# 6-PadsControl_CodSwitch.net
KiCad netlist of a schematic drawn in Altium Designer
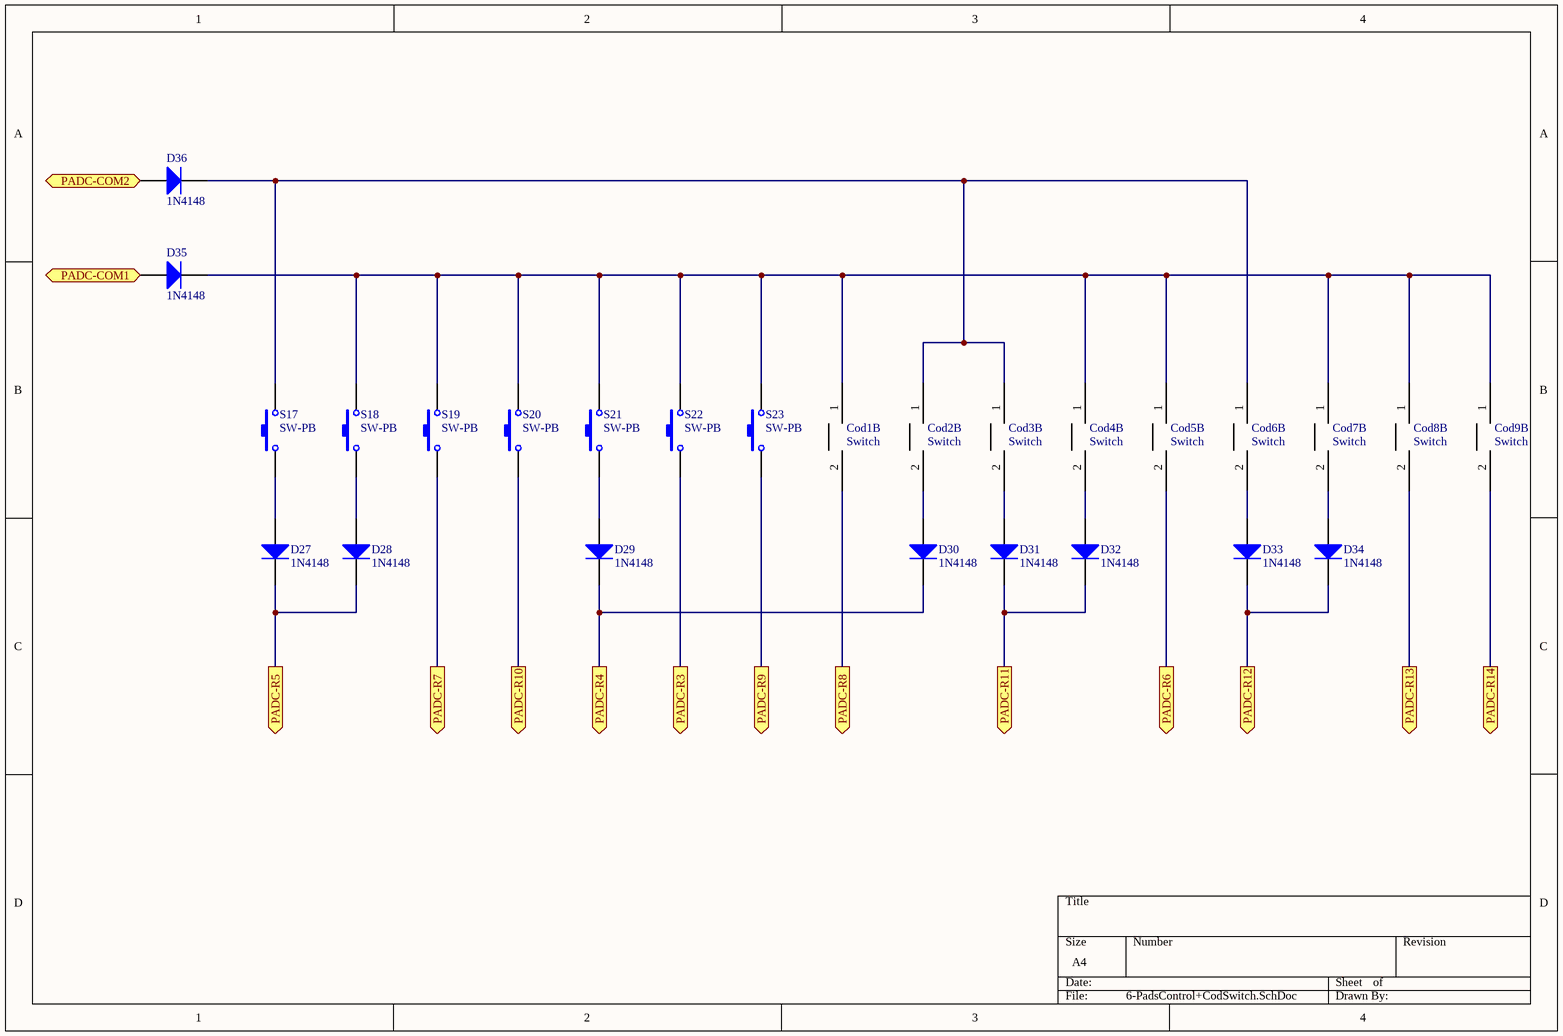
[diagram p0: 6-PadsControl+CodSwitch.SchDoc]

(export (version "E")
  (design (tool "Eeschema 10.0.6"))
  (components
    (comp (ref "Cod1") (value "Switch") (libsource (lib "0x2a002a") (part "Cod")))
    (comp (ref "Cod2") (value "Switch") (libsource (lib "0x2a002a") (part "Cod")))
    (comp (ref "Cod3") (value "Switch") (libsource (lib "0x2a002a") (part "Cod")))
    (comp (ref "Cod4") (value "Switch") (libsource (lib "0x2a002a") (part "Cod")))
    (comp (ref "Cod5") (value "Switch") (libsource (lib "0x2a002a") (part "Cod")))
    (comp (ref "Cod6") (value "Switch") (libsource (lib "0x2a002a") (part "Cod")))
    (comp (ref "Cod7") (value "Switch") (libsource (lib "0x2a002a") (part "Cod")))
    (comp (ref "Cod8") (value "Switch") (libsource (lib "0x2a002a") (part "Cod")))
    (comp (ref "Cod9") (value "Switch") (libsource (lib "0x2a002a") (part "Cod")))
    (comp (ref "D27")
      (value "1N4148")
      (footprint "SMC")
      (description "Default Diode")
      (fields (field (name "PUBLISHER") "Altium Limited"))
      (libsource (lib "Miscellaneous Devices") (part "Diode"))
    )
    (comp (ref "D28")
      (value "1N4148")
      (footprint "SMC")
      (description "Default Diode")
      (fields (field (name "PUBLISHER") "Altium Limited"))
      (libsource (lib "Miscellaneous Devices") (part "Diode"))
    )
    (comp (ref "D29")
      (value "1N4148")
      (footprint "SMC")
      (description "Default Diode")
      (fields (field (name "PUBLISHER") "Altium Limited"))
      (libsource (lib "Miscellaneous Devices") (part "Diode"))
    )
    (comp (ref "D30")
      (value "1N4148")
      (footprint "SMC")
      (description "Default Diode")
      (fields (field (name "PUBLISHER") "Altium Limited"))
      (libsource (lib "Miscellaneous Devices") (part "Diode"))
    )
    (comp (ref "D31")
      (value "1N4148")
      (footprint "SMC")
      (description "Default Diode")
      (fields (field (name "PUBLISHER") "Altium Limited"))
      (libsource (lib "Miscellaneous Devices") (part "Diode"))
    )
    (comp (ref "D32")
      (value "1N4148")
      (footprint "SMC")
      (description "Default Diode")
      (fields (field (name "PUBLISHER") "Altium Limited"))
      (libsource (lib "Miscellaneous Devices") (part "Diode"))
    )
    (comp (ref "D33")
      (value "1N4148")
      (footprint "SMC")
      (description "Default Diode")
      (fields (field (name "PUBLISHER") "Altium Limited"))
      (libsource (lib "Miscellaneous Devices") (part "Diode"))
    )
    (comp (ref "D34")
      (value "1N4148")
      (footprint "SMC")
      (description "Default Diode")
      (fields (field (name "PUBLISHER") "Altium Limited"))
      (libsource (lib "Miscellaneous Devices") (part "Diode"))
    )
    (comp (ref "D35")
      (value "1N4148")
      (footprint "SMC")
      (description "Default Diode")
      (fields (field (name "PUBLISHER") "Altium Limited"))
      (libsource (lib "Miscellaneous Devices") (part "Diode"))
    )
    (comp (ref "D36")
      (value "1N4148")
      (footprint "SMC")
      (description "Default Diode")
      (fields (field (name "PUBLISHER") "Altium Limited"))
      (libsource (lib "Miscellaneous Devices") (part "Diode"))
    )
    (comp (ref "S17")
      (value "SW-PB")
      (footprint "SPST-2")
      (description "Switch")
      (fields (field (name "PUBLISHER") "Altium Limited"))
      (libsource (lib "Miscellaneous Devices") (part "SW-PB"))
    )
    (comp (ref "S18")
      (value "SW-PB")
      (footprint "SPST-2")
      (description "Switch")
      (fields (field (name "PUBLISHER") "Altium Limited"))
      (libsource (lib "Miscellaneous Devices") (part "SW-PB"))
    )
    (comp (ref "S19")
      (value "SW-PB")
      (footprint "SPST-2")
      (description "Switch")
      (fields (field (name "PUBLISHER") "Altium Limited"))
      (libsource (lib "Miscellaneous Devices") (part "SW-PB"))
    )
    (comp (ref "S20")
      (value "SW-PB")
      (footprint "SPST-2")
      (description "Switch")
      (fields (field (name "PUBLISHER") "Altium Limited"))
      (libsource (lib "Miscellaneous Devices") (part "SW-PB"))
    )
    (comp (ref "S21")
      (value "SW-PB")
      (footprint "SPST-2")
      (description "Switch")
      (fields (field (name "PUBLISHER") "Altium Limited"))
      (libsource (lib "Miscellaneous Devices") (part "SW-PB"))
    )
    (comp (ref "S22")
      (value "SW-PB")
      (footprint "SPST-2")
      (description "Switch")
      (fields (field (name "PUBLISHER") "Altium Limited"))
      (libsource (lib "Miscellaneous Devices") (part "SW-PB"))
    )
    (comp (ref "S23")
      (value "SW-PB")
      (footprint "SPST-2")
      (description "Switch")
      (fields (field (name "PUBLISHER") "Altium Limited"))
      (libsource (lib "Miscellaneous Devices") (part "SW-PB"))
    )
  )
  (nets
    (net (code "1") (name "/PADC-COM1") (class "Default")
      (node (ref "D35") (pin "1") (pinfunction "A_1") (pintype "passive"))
    )
    (net (code "2") (name "/PADC-COM2") (class "Default")
      (node (ref "D36") (pin "1") (pinfunction "A_1") (pintype "passive"))
    )
    (net (code "3") (name "/PADC-R3") (class "Default")
      (node (ref "S22") (pin "1") (pinfunction "1_1") (pintype "passive"))
    )
    (net (code "4") (name "/PADC-R4") (class "Default")
      (node (ref "D29") (pin "2") (pinfunction "K_2") (pintype "passive"))
      (node (ref "D30") (pin "2") (pinfunction "K_2") (pintype "passive"))
    )
    (net (code "5") (name "/PADC-R5") (class "Default")
      (node (ref "D27") (pin "2") (pinfunction "K_2") (pintype "passive"))
      (node (ref "D28") (pin "2") (pinfunction "K_2") (pintype "passive"))
    )
    (net (code "6") (name "/PADC-R6") (class "Default") (node (ref "Cod5") (pin "2") (pintype "passive")))
    (net (code "7") (name "/PADC-R7") (class "Default")
      (node (ref "S19") (pin "1") (pinfunction "1_1") (pintype "passive"))
    )
    (net (code "8") (name "/PADC-R8") (class "Default") (node (ref "Cod1") (pin "2") (pintype "passive")))
    (net (code "9") (name "/PADC-R9") (class "Default")
      (node (ref "S23") (pin "1") (pinfunction "1_1") (pintype "passive"))
    )
    (net (code "10") (name "/PADC-R10") (class "Default")
      (node (ref "S20") (pin "1") (pinfunction "1_1") (pintype "passive"))
    )
    (net (code "11") (name "/PADC-R11") (class "Default")
      (node (ref "D31") (pin "2") (pinfunction "K_2") (pintype "passive"))
      (node (ref "D32") (pin "2") (pinfunction "K_2") (pintype "passive"))
    )
    (net (code "12") (name "/PADC-R12") (class "Default")
      (node (ref "D33") (pin "2") (pinfunction "K_2") (pintype "passive"))
      (node (ref "D34") (pin "2") (pinfunction "K_2") (pintype "passive"))
    )
    (net (code "13") (name "/PADC-R13") (class "Default") (node (ref "Cod8") (pin "2") (pintype "passive")))
    (net (code "14") (name "/PADC-R14") (class "Default") (node (ref "Cod9") (pin "2") (pintype "passive")))
    (net (code "15") (name "Net-(D27-A)") (class "Default")
      (node (ref "D27") (pin "1") (pinfunction "A_1") (pintype "passive"))
      (node (ref "S17") (pin "1") (pinfunction "1_1") (pintype "passive"))
    )
    (net (code "16") (name "Net-(D28-A)") (class "Default")
      (node (ref "D28") (pin "1") (pinfunction "A_1") (pintype "passive"))
      (node (ref "S18") (pin "1") (pinfunction "1_1") (pintype "passive"))
    )
    (net (code "17") (name "Net-(D29-A)") (class "Default")
      (node (ref "D29") (pin "1") (pinfunction "A_1") (pintype "passive"))
      (node (ref "S21") (pin "1") (pinfunction "1_1") (pintype "passive"))
    )
    (net (code "18") (name "Net-(D30-A)") (class "Default")
      (node (ref "Cod2") (pin "2") (pintype "passive"))
      (node (ref "D30") (pin "1") (pinfunction "A_1") (pintype "passive"))
    )
    (net (code "19") (name "Net-(D31-A)") (class "Default")
      (node (ref "Cod3") (pin "2") (pintype "passive"))
      (node (ref "D31") (pin "1") (pinfunction "A_1") (pintype "passive"))
    )
    (net (code "20") (name "Net-(D32-A)") (class "Default")
      (node (ref "Cod4") (pin "2") (pintype "passive"))
      (node (ref "D32") (pin "1") (pinfunction "A_1") (pintype "passive"))
    )
    (net (code "21") (name "Net-(D33-A)") (class "Default")
      (node (ref "Cod6") (pin "2") (pintype "passive"))
      (node (ref "D33") (pin "1") (pinfunction "A_1") (pintype "passive"))
    )
    (net (code "22") (name "Net-(D34-A)") (class "Default")
      (node (ref "Cod7") (pin "2") (pintype "passive"))
      (node (ref "D34") (pin "1") (pinfunction "A_1") (pintype "passive"))
    )
    (net (code "23") (name "Net-(D35-K)") (class "Default")
      (node (ref "Cod1") (pin "1") (pintype "passive"))
      (node (ref "Cod4") (pin "1") (pintype "passive"))
      (node (ref "Cod5") (pin "1") (pintype "passive"))
      (node (ref "Cod7") (pin "1") (pintype "passive"))
      (node (ref "Cod8") (pin "1") (pintype "passive"))
      (node (ref "Cod9") (pin "1") (pintype "passive"))
      (node (ref "D35") (pin "2") (pinfunction "K_2") (pintype "passive"))
      (node (ref "S18") (pin "2") (pinfunction "2_2") (pintype "passive"))
      (node (ref "S19") (pin "2") (pinfunction "2_2") (pintype "passive"))
      (node (ref "S20") (pin "2") (pinfunction "2_2") (pintype "passive"))
      (node (ref "S21") (pin "2") (pinfunction "2_2") (pintype "passive"))
      (node (ref "S22") (pin "2") (pinfunction "2_2") (pintype "passive"))
      (node (ref "S23") (pin "2") (pinfunction "2_2") (pintype "passive"))
    )
    (net (code "24") (name "Net-(D36-K)") (class "Default")
      (node (ref "Cod2") (pin "1") (pintype "passive"))
      (node (ref "Cod3") (pin "1") (pintype "passive"))
      (node (ref "Cod6") (pin "1") (pintype "passive"))
      (node (ref "D36") (pin "2") (pinfunction "K_2") (pintype "passive"))
      (node (ref "S17") (pin "2") (pinfunction "2_2") (pintype "passive"))
    )
  )
)
